# charge.net
KiCad netlist of a schematic drawn in EAGLE
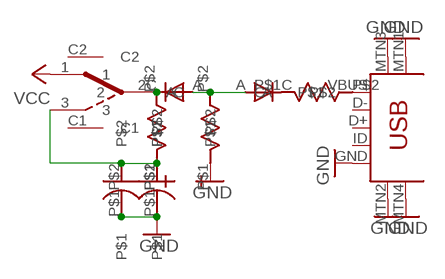
[diagram p0: schematic, sheet 1]

(export (version "E")
  (design (tool "Eeschema 10.0.6"))
  (components
    (comp (ref "U$1")
      (value "R-7")
      (footprint "eagle-import:R-7")
      (libsource (lib "eagle-import") (part "R-7"))
    )
    (comp (ref "U$2")
      (value "NICHICON_12F")
      (footprint "eagle-import:NICHICON_10X30")
      (libsource (lib "eagle-import") (part "NICHICON_12F"))
    )
    (comp (ref "U$3")
      (value "NICHICON_12F")
      (footprint "eagle-import:NICHICON_10X30")
      (libsource (lib "eagle-import") (part "NICHICON_12F"))
    )
    (comp (ref "U$5")
      (value "D-6")
      (footprint "eagle-import:D-7.5")
      (libsource (lib "eagle-import") (part "D-6"))
    )
    (comp (ref "U$6")
      (value "SPST_PTH")
      (footprint "eagle-import:SWITCH2")
      (libsource (lib "eagle-import") (part "SPST_PTH"))
    )
    (comp (ref "U$7")
      (value "USB-MINIB-5PIN")
      (footprint "eagle-import:USB-MINIB")
      (libsource (lib "eagle-import") (part "USB-MINIB-5PIN"))
    )
    (comp (ref "U$8")
      (value "R-7")
      (footprint "eagle-import:R-7")
      (libsource (lib "eagle-import") (part "R-7"))
    )
    (comp (ref "U$9")
      (value "D-6")
      (footprint "eagle-import:D-7.5")
      (libsource (lib "eagle-import") (part "D-6"))
    )
    (comp (ref "U$10")
      (value "R-7")
      (footprint "eagle-import:R-7")
      (libsource (lib "eagle-import") (part "R-7"))
    )
  )
  (nets
    (net (code "1") (name "GND") (class "Default")
      (node (ref "U$10") (pin "P$1") (pinfunction "P$1_P$1") (pintype "bidirectional"))
      (node (ref "U$2") (pin "P$1") (pinfunction "P$1_P$1") (pintype "bidirectional"))
      (node (ref "U$3") (pin "P$1") (pinfunction "P$1_P$1") (pintype "bidirectional"))
      (node (ref "U$7") (pin "GND") (pinfunction "GND_GND") (pintype "bidirectional"))
      (node (ref "U$7") (pin "MTN1") (pinfunction "MTN2_MTN1") (pintype "bidirectional"))
      (node (ref "U$7") (pin "MTN2") (pinfunction "MTN3_MTN2") (pintype "bidirectional"))
      (node (ref "U$7") (pin "MTN3") (pinfunction "MTN1_MTN3") (pintype "bidirectional"))
      (node (ref "U$7") (pin "MTN4") (pinfunction "MTN4_MTN4") (pintype "bidirectional"))
    )
    (net (code "2") (name "Net-(U$1-PadP$1)") (class "Default")
      (node (ref "U$1") (pin "P$1") (pinfunction "P$1_P$1") (pintype "bidirectional"))
      (node (ref "U$5") (pin "C") (pinfunction "C_C") (pintype "bidirectional"))
    )
    (net (code "3") (name "Net-(U$1-PadP$2)") (class "Default")
      (node (ref "U$1") (pin "P$2") (pinfunction "P$2_P$2") (pintype "bidirectional"))
      (node (ref "U$7") (pin "VBUS") (pinfunction "VBUS_VBUS") (pintype "bidirectional"))
    )
    (net (code "4") (name "Net-(U$2-PadP$2)") (class "Default")
      (node (ref "U$2") (pin "P$2") (pinfunction "P$2_P$2") (pintype "bidirectional"))
      (node (ref "U$3") (pin "P$2") (pinfunction "P$2_P$2") (pintype "bidirectional"))
      (node (ref "U$6") (pin "3") (pinfunction "3_3") (pintype "bidirectional"))
      (node (ref "U$8") (pin "P$1") (pinfunction "P$1_P$1") (pintype "bidirectional"))
    )
    (net (code "5") (name "Net-(U$6-Pad2)") (class "Default")
      (node (ref "U$6") (pin "2") (pinfunction "2_2") (pintype "bidirectional"))
      (node (ref "U$8") (pin "P$2") (pinfunction "P$2_P$2") (pintype "bidirectional"))
      (node (ref "U$9") (pin "C") (pinfunction "C_C") (pintype "bidirectional"))
    )
    (net (code "6") (name "Net-(U$10-PadP$2)") (class "Default")
      (node (ref "U$10") (pin "P$2") (pinfunction "P$2_P$2") (pintype "bidirectional"))
      (node (ref "U$5") (pin "A") (pinfunction "A_A") (pintype "bidirectional"))
      (node (ref "U$9") (pin "A") (pinfunction "A_A") (pintype "bidirectional"))
    )
    (net (code "7") (name "VCC") (class "Default")
      (node (ref "U$6") (pin "1") (pinfunction "1_1") (pintype "bidirectional"))
    )
    (net (code "8") (name "unconnected-(U$6-PadC1)") (class "Default")
      (node (ref "U$6") (pin "C1") (pinfunction "C1_C1") (pintype "bidirectional"))
    )
    (net (code "9") (name "unconnected-(U$6-PadC2)") (class "Default")
      (node (ref "U$6") (pin "C2") (pinfunction "C2_C2") (pintype "bidirectional"))
    )
    (net (code "10") (name "unconnected-(U$7-PadD+)") (class "Default")
      (node (ref "U$7") (pin "D+") (pinfunction "D+_D+") (pintype "bidirectional"))
    )
    (net (code "11") (name "unconnected-(U$7-PadD-)") (class "Default")
      (node (ref "U$7") (pin "D-") (pinfunction "D-_D-") (pintype "bidirectional"))
    )
    (net (code "12") (name "unconnected-(U$7-PadID)") (class "Default")
      (node (ref "U$7") (pin "ID") (pinfunction "ID_ID") (pintype "bidirectional"))
    )
  )
)
